# hextokWings04a.net
KiCad netlist of a schematic drawn in EAGLE
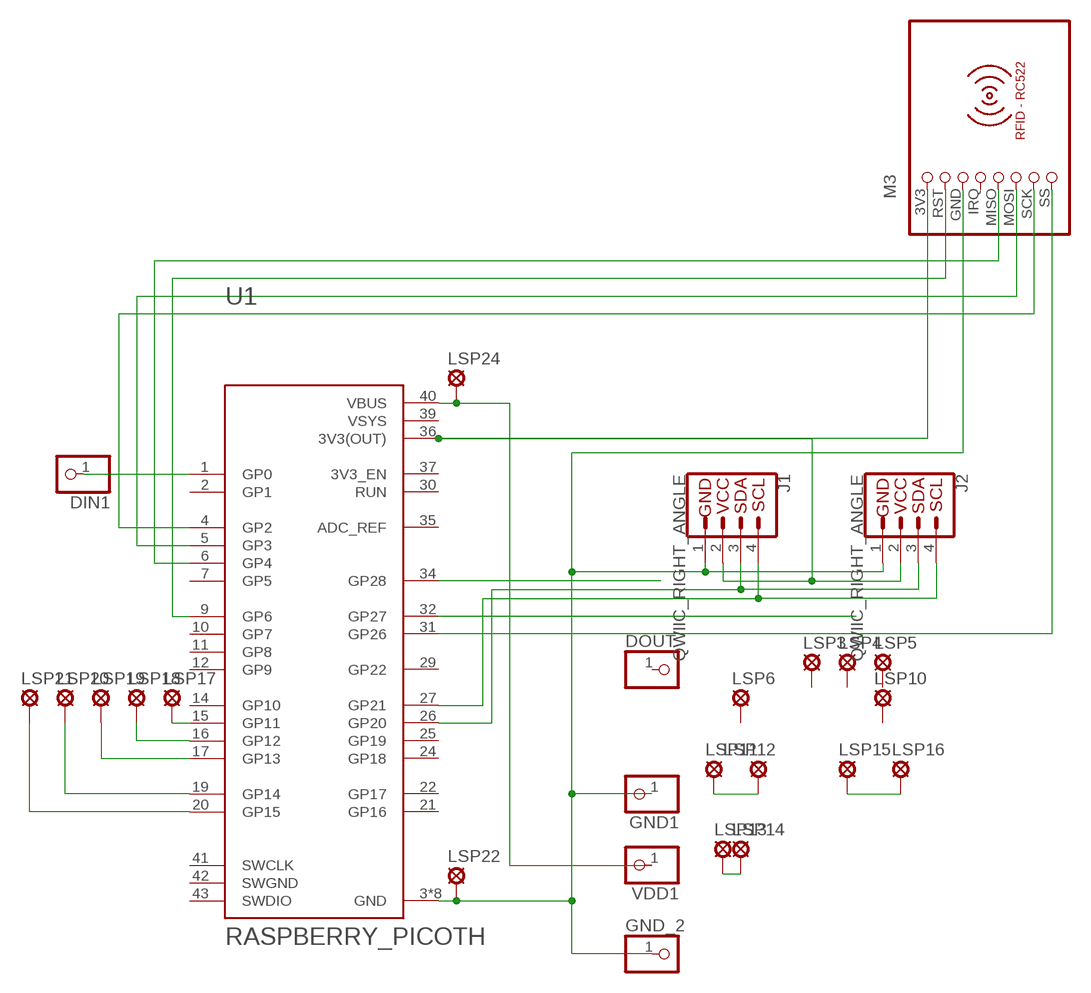
[diagram p0: schematic, sheet 1]

(export (version "E")
  (design (tool "Eeschema 10.0.6"))
  (components
    (comp (ref "DIN1")
      (value "PINHD-1X1CB")
      (footprint "eagle-import:1X01-CLEANBIG")
      (libsource (lib "eagle-import") (part "PINHD-1X1CB"))
    )
    (comp (ref "DOUT")
      (value "PINHD-1X1CB")
      (footprint "eagle-import:1X01-CLEANBIG")
      (libsource (lib "eagle-import") (part "PINHD-1X1CB"))
    )
    (comp (ref "GND1")
      (value "PINHD-1X1CB")
      (footprint "eagle-import:1X01-CLEANBIG")
      (libsource (lib "eagle-import") (part "PINHD-1X1CB"))
    )
    (comp (ref "GND_2")
      (value "PINHD-1X1CB")
      (footprint "eagle-import:1X01-CLEANBIG")
      (libsource (lib "eagle-import") (part "PINHD-1X1CB"))
    )
    (comp (ref "J1")
      (value "QWIIC_RIGHT_ANGLE")
      (footprint "eagle-import:JST04_1MM_RA")
      (libsource (lib "eagle-import") (part "QWIIC_CONNECTORJS-1MM"))
    )
    (comp (ref "J2")
      (value "QWIIC_RIGHT_ANGLE")
      (footprint "eagle-import:JST04_1MM_RA")
      (libsource (lib "eagle-import") (part "QWIIC_CONNECTORJS-1MM"))
    )
    (comp (ref "LSP3")
      (value "LSP10")
      (footprint "eagle-import:LSP10")
      (libsource (lib "eagle-import") (part "LSP10"))
    )
    (comp (ref "LSP4")
      (value "LSP10")
      (footprint "eagle-import:LSP10")
      (libsource (lib "eagle-import") (part "LSP10"))
    )
    (comp (ref "LSP5")
      (value "LSP10")
      (footprint "eagle-import:LSP10")
      (libsource (lib "eagle-import") (part "LSP10"))
    )
    (comp (ref "LSP6")
      (value "LSP10")
      (footprint "eagle-import:LSP10")
      (libsource (lib "eagle-import") (part "LSP10"))
    )
    (comp (ref "LSP10")
      (value "LSP10")
      (footprint "eagle-import:LSP10")
      (libsource (lib "eagle-import") (part "LSP10"))
    )
    (comp (ref "LSP11")
      (value "LSP10")
      (footprint "eagle-import:LSP10")
      (libsource (lib "eagle-import") (part "LSP10"))
    )
    (comp (ref "LSP12")
      (value "LSP10")
      (footprint "eagle-import:LSP10")
      (libsource (lib "eagle-import") (part "LSP10"))
    )
    (comp (ref "LSP13")
      (value "LSP10")
      (footprint "eagle-import:LSP10")
      (libsource (lib "eagle-import") (part "LSP10"))
    )
    (comp (ref "LSP14")
      (value "LSP10")
      (footprint "eagle-import:LSP10")
      (libsource (lib "eagle-import") (part "LSP10"))
    )
    (comp (ref "LSP15")
      (value "LSP10")
      (footprint "eagle-import:LSP10")
      (libsource (lib "eagle-import") (part "LSP10"))
    )
    (comp (ref "LSP16")
      (value "LSP10")
      (footprint "eagle-import:LSP10")
      (libsource (lib "eagle-import") (part "LSP10"))
    )
    (comp (ref "LSP17")
      (value "LSP10")
      (footprint "eagle-import:LSP10")
      (libsource (lib "eagle-import") (part "LSP10"))
    )
    (comp (ref "LSP18")
      (value "LSP10")
      (footprint "eagle-import:LSP10")
      (libsource (lib "eagle-import") (part "LSP10"))
    )
    (comp (ref "LSP19")
      (value "LSP10")
      (footprint "eagle-import:LSP10")
      (libsource (lib "eagle-import") (part "LSP10"))
    )
    (comp (ref "LSP20")
      (value "LSP10")
      (footprint "eagle-import:LSP10")
      (libsource (lib "eagle-import") (part "LSP10"))
    )
    (comp (ref "LSP21")
      (value "LSP10")
      (footprint "eagle-import:LSP10")
      (libsource (lib "eagle-import") (part "LSP10"))
    )
    (comp (ref "LSP22")
      (value "LSP10")
      (footprint "eagle-import:LSP10")
      (libsource (lib "eagle-import") (part "LSP10"))
    )
    (comp (ref "LSP24")
      (value "LSP10")
      (footprint "eagle-import:LSP10")
      (libsource (lib "eagle-import") (part "LSP10"))
    )
    (comp (ref "M3")
      (value "RFID-RC522")
      (footprint "eagle-import:RFID-RC522")
      (libsource (lib "eagle-import") (part "RFID-RC522"))
    )
    (comp (ref "U1")
      (value "RASPBERRY_PICOTH")
      (footprint "eagle-import:PICO-PKG-TH")
      (libsource (lib "eagle-import") (part "RASPBERRY_PICOTH"))
    )
    (comp (ref "VDD1")
      (value "PINHD-1X1CB")
      (footprint "eagle-import:1X01-CLEANBIG")
      (libsource (lib "eagle-import") (part "PINHD-1X1CB"))
    )
  )
  (nets
    (net (code "1") (name "/SWGND") (class "Default")
      (node (ref "U1") (pin "42") (pinfunction "SWGND_42") (pintype "power_in"))
    )
    (net (code "2") (name "/VSYS") (class "Default")
      (node (ref "U1") (pin "39") (pinfunction "VSYS_39") (pintype "power_in"))
    )
    (net (code "3") (name "Net-(LSP11-PadMP)") (class "Default")
      (node (ref "LSP11") (pin "MP") (pinfunction "MP_MP") (pintype "passive"))
      (node (ref "LSP12") (pin "MP") (pinfunction "MP_MP") (pintype "passive"))
    )
    (net (code "4") (name "Net-(LSP13-PadMP)") (class "Default")
      (node (ref "LSP13") (pin "MP") (pinfunction "MP_MP") (pintype "passive"))
      (node (ref "LSP14") (pin "MP") (pinfunction "MP_MP") (pintype "passive"))
    )
    (net (code "5") (name "Net-(LSP15-PadMP)") (class "Default")
      (node (ref "LSP15") (pin "MP") (pinfunction "MP_MP") (pintype "passive"))
      (node (ref "LSP16") (pin "MP") (pinfunction "MP_MP") (pintype "passive"))
    )
    (net (code "6") (name "Net-(M3-1)") (class "Default")
      (node (ref "J1") (pin "2") (pinfunction "2_2") (pintype "power_in"))
      (node (ref "J2") (pin "2") (pinfunction "2_2") (pintype "power_in"))
      (node (ref "M3") (pin "3V3") (pinfunction "1_3V3") (pintype "passive"))
      (node (ref "U1") (pin "36") (pinfunction "3V3(OUT)_36") (pintype "power_in"))
    )
    (net (code "7") (name "Net-(M3-2)") (class "Default")
      (node (ref "M3") (pin "RST") (pinfunction "2_RST") (pintype "passive"))
      (node (ref "U1") (pin "9") (pinfunction "GP6_9") (pintype "bidirectional"))
    )
    (net (code "8") (name "Net-(M3-3)") (class "Default")
      (node (ref "GND1") (pin "1") (pinfunction "1_1") (pintype "passive"))
      (node (ref "GND_2") (pin "1") (pinfunction "1_1") (pintype "passive"))
      (node (ref "J1") (pin "1") (pinfunction "1_1") (pintype "power_in"))
      (node (ref "J2") (pin "1") (pinfunction "1_1") (pintype "power_in"))
      (node (ref "LSP22") (pin "MP") (pinfunction "MP_MP") (pintype "passive"))
      (node (ref "M3") (pin "GND") (pinfunction "3_GND") (pintype "passive"))
      (node (ref "U1") (pin "13") (pinfunction "GND_13") (pintype "power_in"))
      (node (ref "U1") (pin "18") (pinfunction "GND_18") (pintype "power_in"))
      (node (ref "U1") (pin "23") (pinfunction "GND_23") (pintype "power_in"))
      (node (ref "U1") (pin "28") (pinfunction "GND_28") (pintype "power_in"))
      (node (ref "U1") (pin "3") (pinfunction "GND_3") (pintype "power_in"))
      (node (ref "U1") (pin "33") (pinfunction "GND_33") (pintype "power_in"))
      (node (ref "U1") (pin "38") (pinfunction "GND_38") (pintype "power_in"))
      (node (ref "U1") (pin "8") (pinfunction "GND_8") (pintype "power_in"))
    )
    (net (code "9") (name "Net-(M3-5)") (class "Default")
      (node (ref "M3") (pin "MISO") (pinfunction "5_MISO") (pintype "passive"))
      (node (ref "U1") (pin "6") (pinfunction "GP4_6") (pintype "bidirectional"))
    )
    (net (code "10") (name "Net-(M3-6)") (class "Default")
      (node (ref "M3") (pin "MOSI") (pinfunction "6_MOSI") (pintype "passive"))
      (node (ref "U1") (pin "5") (pinfunction "GP3_5") (pintype "bidirectional"))
    )
    (net (code "11") (name "Net-(M3-7)") (class "Default")
      (node (ref "M3") (pin "SCK") (pinfunction "7_SCK") (pintype "passive"))
      (node (ref "U1") (pin "4") (pinfunction "GP2_4") (pintype "bidirectional"))
    )
    (net (code "12") (name "Net-(M3-8)") (class "Default")
      (node (ref "M3") (pin "SS") (pinfunction "8_SS") (pintype "passive"))
      (node (ref "U1") (pin "31") (pinfunction "GP26_31") (pintype "bidirectional"))
    )
    (net (code "13") (name "Net-(U1-GP0)") (class "Default")
      (node (ref "DIN1") (pin "1") (pinfunction "1_1") (pintype "passive"))
      (node (ref "U1") (pin "1") (pinfunction "GP0_1") (pintype "bidirectional"))
    )
    (net (code "14") (name "Net-(U1-GP11)") (class "Default")
      (node (ref "LSP17") (pin "MP") (pinfunction "MP_MP") (pintype "passive"))
      (node (ref "U1") (pin "15") (pinfunction "GP11_15") (pintype "bidirectional"))
    )
    (net (code "15") (name "Net-(U1-GP12)") (class "Default")
      (node (ref "LSP18") (pin "MP") (pinfunction "MP_MP") (pintype "passive"))
      (node (ref "U1") (pin "16") (pinfunction "GP12_16") (pintype "bidirectional"))
    )
    (net (code "16") (name "Net-(U1-GP13)") (class "Default")
      (node (ref "LSP19") (pin "MP") (pinfunction "MP_MP") (pintype "passive"))
      (node (ref "U1") (pin "17") (pinfunction "GP13_17") (pintype "bidirectional"))
    )
    (net (code "17") (name "Net-(U1-GP14)") (class "Default")
      (node (ref "LSP20") (pin "MP") (pinfunction "MP_MP") (pintype "passive"))
      (node (ref "U1") (pin "19") (pinfunction "GP14_19") (pintype "bidirectional"))
    )
    (net (code "18") (name "Net-(U1-GP15)") (class "Default")
      (node (ref "LSP21") (pin "MP") (pinfunction "MP_MP") (pintype "passive"))
      (node (ref "U1") (pin "20") (pinfunction "GP15_20") (pintype "bidirectional"))
    )
    (net (code "19") (name "Net-(U1-GP20)") (class "Default")
      (node (ref "J1") (pin "3") (pinfunction "3_3") (pintype "passive"))
      (node (ref "J2") (pin "3") (pinfunction "3_3") (pintype "passive"))
      (node (ref "U1") (pin "26") (pinfunction "GP20_26") (pintype "bidirectional"))
    )
    (net (code "20") (name "Net-(U1-GP21)") (class "Default")
      (node (ref "J1") (pin "4") (pinfunction "4_4") (pintype "passive"))
      (node (ref "J2") (pin "4") (pinfunction "4_4") (pintype "passive"))
      (node (ref "U1") (pin "27") (pinfunction "GP21_27") (pintype "bidirectional"))
    )
    (net (code "21") (name "Net-(U1-VBUS)") (class "Default")
      (node (ref "LSP24") (pin "MP") (pinfunction "MP_MP") (pintype "passive"))
      (node (ref "U1") (pin "40") (pinfunction "VBUS_40") (pintype "power_in"))
      (node (ref "VDD1") (pin "1") (pinfunction "1_1") (pintype "passive"))
    )
    (net (code "22") (name "unconnected-(DOUT-Pad1)") (class "Default")
      (node (ref "DOUT") (pin "1") (pinfunction "1_1") (pintype "passive"))
    )
    (net (code "23") (name "unconnected-(LSP3-PadMP)") (class "Default")
      (node (ref "LSP3") (pin "MP") (pinfunction "MP_MP") (pintype "passive"))
    )
    (net (code "24") (name "unconnected-(LSP4-PadMP)") (class "Default")
      (node (ref "LSP4") (pin "MP") (pinfunction "MP_MP") (pintype "passive"))
    )
    (net (code "25") (name "unconnected-(LSP5-PadMP)") (class "Default")
      (node (ref "LSP5") (pin "MP") (pinfunction "MP_MP") (pintype "passive"))
    )
    (net (code "26") (name "unconnected-(LSP6-PadMP)") (class "Default")
      (node (ref "LSP6") (pin "MP") (pinfunction "MP_MP") (pintype "passive"))
    )
    (net (code "27") (name "unconnected-(LSP10-PadMP)") (class "Default")
      (node (ref "LSP10") (pin "MP") (pinfunction "MP_MP") (pintype "passive"))
    )
    (net (code "28") (name "unconnected-(M3-4-PadIRQ)") (class "Default")
      (node (ref "M3") (pin "IRQ") (pinfunction "4_IRQ") (pintype "passive"))
    )
    (net (code "29") (name "unconnected-(U1-3V3_EN-Pad37)") (class "Default")
      (node (ref "U1") (pin "37") (pinfunction "3V3_EN_37") (pintype "input"))
    )
    (net (code "30") (name "unconnected-(U1-ADC_REF-Pad35)") (class "Default")
      (node (ref "U1") (pin "35") (pinfunction "ADC_REF_35") (pintype "input"))
    )
    (net (code "31") (name "unconnected-(U1-GP1-Pad2)") (class "Default")
      (node (ref "U1") (pin "2") (pinfunction "GP1_2") (pintype "bidirectional"))
    )
    (net (code "32") (name "unconnected-(U1-GP5-Pad7)") (class "Default")
      (node (ref "U1") (pin "7") (pinfunction "GP5_7") (pintype "bidirectional"))
    )
    (net (code "33") (name "unconnected-(U1-GP7-Pad10)") (class "Default")
      (node (ref "U1") (pin "10") (pinfunction "GP7_10") (pintype "bidirectional"))
    )
    (net (code "34") (name "unconnected-(U1-GP8-Pad11)") (class "Default")
      (node (ref "U1") (pin "11") (pinfunction "GP8_11") (pintype "bidirectional"))
    )
    (net (code "35") (name "unconnected-(U1-GP9-Pad12)") (class "Default")
      (node (ref "U1") (pin "12") (pinfunction "GP9_12") (pintype "bidirectional"))
    )
    (net (code "36") (name "unconnected-(U1-GP10-Pad14)") (class "Default")
      (node (ref "U1") (pin "14") (pinfunction "GP10_14") (pintype "bidirectional"))
    )
    (net (code "37") (name "unconnected-(U1-GP16-Pad21)") (class "Default")
      (node (ref "U1") (pin "21") (pinfunction "GP16_21") (pintype "bidirectional"))
    )
    (net (code "38") (name "unconnected-(U1-GP17-Pad22)") (class "Default")
      (node (ref "U1") (pin "22") (pinfunction "GP17_22") (pintype "bidirectional"))
    )
    (net (code "39") (name "unconnected-(U1-GP18-Pad24)") (class "Default")
      (node (ref "U1") (pin "24") (pinfunction "GP18_24") (pintype "bidirectional"))
    )
    (net (code "40") (name "unconnected-(U1-GP19-Pad25)") (class "Default")
      (node (ref "U1") (pin "25") (pinfunction "GP19_25") (pintype "bidirectional"))
    )
    (net (code "41") (name "unconnected-(U1-GP22-Pad29)") (class "Default")
      (node (ref "U1") (pin "29") (pinfunction "GP22_29") (pintype "bidirectional"))
    )
    (net (code "42") (name "unconnected-(U1-GP27-Pad32)") (class "Default")
      (node (ref "U1") (pin "32") (pinfunction "GP27_32") (pintype "bidirectional"))
    )
    (net (code "43") (name "unconnected-(U1-GP28-Pad34)") (class "Default")
      (node (ref "U1") (pin "34") (pinfunction "GP28_34") (pintype "bidirectional"))
    )
    (net (code "44") (name "unconnected-(U1-RUN-Pad30)") (class "Default")
      (node (ref "U1") (pin "30") (pinfunction "RUN_30") (pintype "input"))
    )
    (net (code "45") (name "unconnected-(U1-SWCLK-Pad41)") (class "Default")
      (node (ref "U1") (pin "41") (pinfunction "SWCLK_41") (pintype "input"))
    )
    (net (code "46") (name "unconnected-(U1-SWDIO-Pad43)") (class "Default")
      (node (ref "U1") (pin "43") (pinfunction "SWDIO_43") (pintype "bidirectional"))
    )
  )
)
